# SCH___2025-06-27.net
KiCad netlist of a schematic drawn in EasyEDA
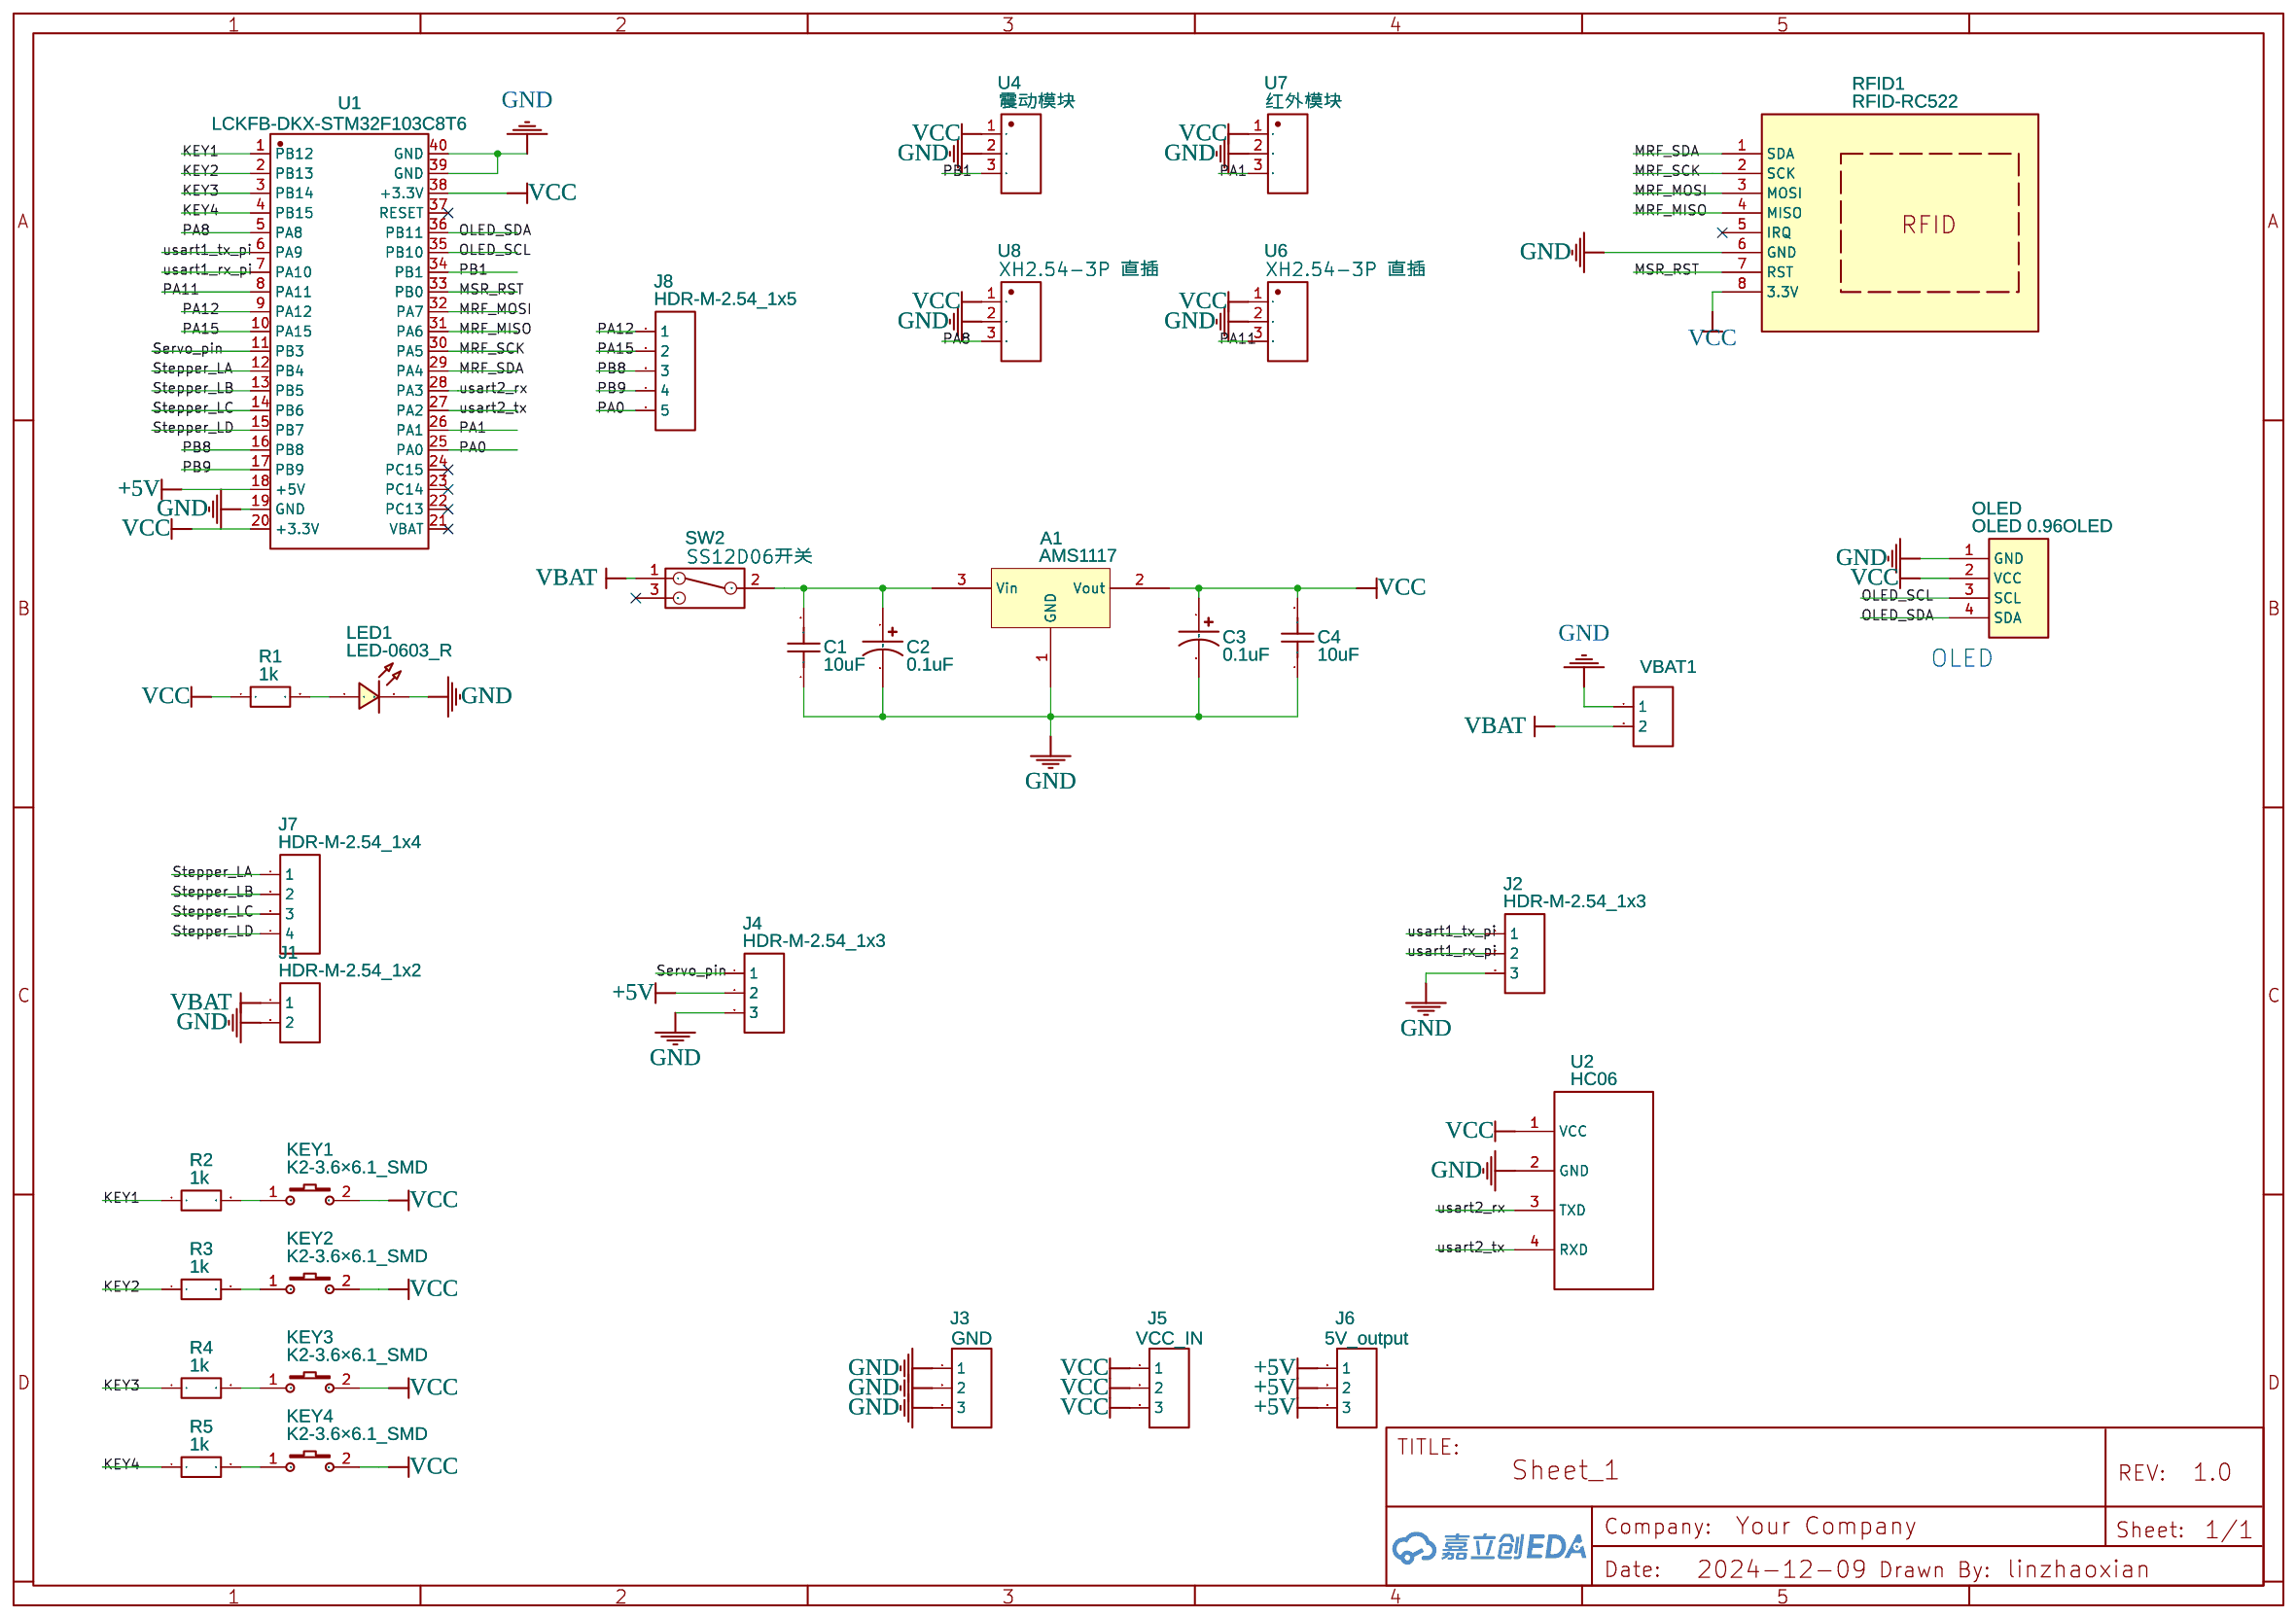
[diagram p0: schematic sheet]

(export (version "E")
  (design (tool "Eeschema 10.0.6"))
  (components
    (comp (ref "A1") (value "AMS1117") (libsource (lib "") (part "AMS1117")))
    (comp (ref "C1") (value "10uF") (libsource (lib "") (part "C_0603_US")))
    (comp (ref "C2") (value "0.1uF") (libsource (lib "") (part "C_Tan_SMD_A_US")))
    (comp (ref "C3") (value "0.1uF") (libsource (lib "") (part "C_Tan_SMD_A_US")))
    (comp (ref "C4") (value "10uF") (libsource (lib "") (part "C_0603_US")))
    (comp (ref "J1") (value "HDR-M-2.54_1x2") (libsource (lib "") (part "HDR-M-2.54_1x2")))
    (comp (ref "J2") (value "HDR-M-2.54_1x3") (libsource (lib "") (part "HDR-M-2.54_1x3")))
    (comp (ref "J3") (value "GND") (libsource (lib "") (part "HDR-M-2.54_1x3")))
    (comp (ref "J4") (value "HDR-M-2.54_1x3") (libsource (lib "") (part "HDR-M-2.54_1x3")))
    (comp (ref "J5") (value "VCC_IN") (libsource (lib "") (part "HDR-M-2.54_1x3")))
    (comp (ref "J6") (value "5V_output") (libsource (lib "") (part "HDR-M-2.54_1x3")))
    (comp (ref "J7") (value "HDR-M-2.54_1x4") (libsource (lib "") (part "HDR-M-2.54_1x4")))
    (comp (ref "J8") (value "HDR-M-2.54_1x5") (libsource (lib "") (part "HDR-M-2.54_1x5")))
    (comp (ref "KEY1")
      (value "K2-3.6×6.1_SMD")
      (fields (field (name "Manufacturer Part") "K2-1107ST-A4SW-06"))
      (libsource (lib "") (part "K2-3.6×6.1_SMD"))
    )
    (comp (ref "KEY2")
      (value "K2-3.6×6.1_SMD")
      (fields (field (name "Manufacturer Part") "K2-1107ST-A4SW-06"))
      (libsource (lib "") (part "K2-3.6×6.1_SMD"))
    )
    (comp (ref "KEY3")
      (value "K2-3.6×6.1_SMD")
      (fields (field (name "Manufacturer Part") "K2-1107ST-A4SW-06"))
      (libsource (lib "") (part "K2-3.6×6.1_SMD"))
    )
    (comp (ref "KEY4")
      (value "K2-3.6×6.1_SMD")
      (fields (field (name "Manufacturer Part") "K2-1107ST-A4SW-06"))
      (libsource (lib "") (part "K2-3.6×6.1_SMD"))
    )
    (comp (ref "LED1")
      (value "LED-0603_R")
      (fields
        (field (name "Manufacturer Part") "19-217/R6C-AL1M2VY/3T")
        (field (name "Manufacturer") "EVERLIGHT(台湾亿光)")
      )
      (libsource (lib "") (part "LED-0603_R"))
    )
    (comp (ref "OLED") (value "OLED 0.96OLED") (libsource (lib "") (part "OLED 0.96OLED")))
    (comp (ref "R1") (value "1k") (libsource (lib "") (part "R_0805_EU")))
    (comp (ref "R2") (value "1k") (libsource (lib "") (part "R_0805_EU")))
    (comp (ref "R3") (value "1k") (libsource (lib "") (part "R_0805_EU")))
    (comp (ref "R4") (value "1k") (libsource (lib "") (part "R_0805_EU")))
    (comp (ref "R5") (value "1k") (libsource (lib "") (part "R_0805_EU")))
    (comp (ref "RFID1") (value "RFID-RC522") (libsource (lib "") (part "RFID-RC522")))
    (comp (ref "SW2") (value "SS12D06开关") (libsource (lib "") (part "SS12D06开关")))
    (comp (ref "U1")
      (value "LCKFB-DKX-STM32F103C8T6")
      (fields (field (name "Manufacturer") "立创开发板"))
      (libsource (lib "") (part "LCKFB-DKX-STM32F103C8T6"))
    )
    (comp (ref "U2") (value "HC06") (libsource (lib "") (part "HC06")))
    (comp (ref "U4")
      (value "震动模块")
      (fields (field (name "Manufacturer Part") "XH2.54-3P 直插"))
      (libsource (lib "") (part "XH2.54-3P 直插"))
    )
    (comp (ref "U6") (value "XH2.54-3P 直插") (libsource (lib "") (part "XH2.54-3P 直插")))
    (comp (ref "U7")
      (value "红外模块")
      (fields (field (name "Manufacturer Part") "XH2.54-3P 直插"))
      (libsource (lib "") (part "XH2.54-3P 直插"))
    )
    (comp (ref "U8") (value "XH2.54-3P 直插") (libsource (lib "") (part "XH2.54-3P 直插")))
    (comp (ref "VBAT1") (value "端子") (libsource (lib "") (part "CONN-TH_2P-P5.00")))
  )
  (nets
    (net (code "1") (name "+5V") (class "Default")
      (node (ref "J4") (pin "2") (pinfunction "2_2") (pintype "input"))
      (node (ref "J6") (pin "1") (pinfunction "1_1") (pintype "input"))
      (node (ref "J6") (pin "2") (pinfunction "2_2") (pintype "input"))
      (node (ref "J6") (pin "3") (pinfunction "3_3") (pintype "input"))
      (node (ref "U1") (pin "18") (pinfunction "+5V_18") (pintype "unspecified"))
    )
    (net (code "2") (name "/KEY1") (class "Default")
      (node (ref "R2") (pin "1") (pinfunction "1_1") (pintype "unspecified"))
      (node (ref "U1") (pin "1") (pinfunction "PB12_1") (pintype "unspecified"))
    )
    (net (code "3") (name "/KEY2") (class "Default")
      (node (ref "R3") (pin "1") (pinfunction "1_1") (pintype "unspecified"))
      (node (ref "U1") (pin "2") (pinfunction "PB13_2") (pintype "unspecified"))
    )
    (net (code "4") (name "/KEY3") (class "Default")
      (node (ref "R4") (pin "1") (pinfunction "1_1") (pintype "unspecified"))
      (node (ref "U1") (pin "3") (pinfunction "PB14_3") (pintype "unspecified"))
    )
    (net (code "5") (name "/KEY4") (class "Default")
      (node (ref "R5") (pin "1") (pinfunction "1_1") (pintype "unspecified"))
      (node (ref "U1") (pin "4") (pinfunction "PB15_4") (pintype "unspecified"))
    )
    (net (code "6") (name "/MRF_MISO") (class "Default")
      (node (ref "RFID1") (pin "4") (pinfunction "MISO_4") (pintype "unspecified"))
      (node (ref "U1") (pin "31") (pinfunction "PA6_31") (pintype "unspecified"))
    )
    (net (code "7") (name "/MRF_MOSI") (class "Default")
      (node (ref "RFID1") (pin "3") (pinfunction "MOSI_3") (pintype "unspecified"))
      (node (ref "U1") (pin "32") (pinfunction "PA7_32") (pintype "unspecified"))
    )
    (net (code "8") (name "/MRF_SCK") (class "Default")
      (node (ref "RFID1") (pin "2") (pinfunction "SCK_2") (pintype "unspecified"))
      (node (ref "U1") (pin "30") (pinfunction "PA5_30") (pintype "unspecified"))
    )
    (net (code "9") (name "/MRF_SDA") (class "Default")
      (node (ref "RFID1") (pin "1") (pinfunction "SDA_1") (pintype "unspecified"))
      (node (ref "U1") (pin "29") (pinfunction "PA4_29") (pintype "unspecified"))
    )
    (net (code "10") (name "/MSR_RST") (class "Default")
      (node (ref "RFID1") (pin "7") (pinfunction "RST_7") (pintype "unspecified"))
      (node (ref "U1") (pin "33") (pinfunction "PB0_33") (pintype "unspecified"))
    )
    (net (code "11") (name "/OLED_SCL") (class "Default")
      (node (ref "OLED") (pin "3") (pinfunction "SCL_3") (pintype "unspecified"))
      (node (ref "U1") (pin "35") (pinfunction "PB10_35") (pintype "unspecified"))
    )
    (net (code "12") (name "/OLED_SDA") (class "Default")
      (node (ref "OLED") (pin "4") (pinfunction "SDA_4") (pintype "unspecified"))
      (node (ref "U1") (pin "36") (pinfunction "PB11_36") (pintype "unspecified"))
    )
    (net (code "13") (name "/PA0") (class "Default")
      (node (ref "J8") (pin "5") (pinfunction "5_5") (pintype "unspecified"))
      (node (ref "U1") (pin "25") (pinfunction "PA0_25") (pintype "unspecified"))
    )
    (net (code "14") (name "/PA1") (class "Default")
      (node (ref "U1") (pin "26") (pinfunction "PA1_26") (pintype "unspecified"))
      (node (ref "U7") (pin "3") (pinfunction "3_3") (pintype "unspecified"))
    )
    (net (code "15") (name "/PA8") (class "Default")
      (node (ref "U1") (pin "5") (pinfunction "PA8_5") (pintype "unspecified"))
      (node (ref "U8") (pin "3") (pinfunction "3_3") (pintype "unspecified"))
    )
    (net (code "16") (name "/PA11") (class "Default")
      (node (ref "U1") (pin "8") (pinfunction "PA11_8") (pintype "unspecified"))
      (node (ref "U6") (pin "3") (pinfunction "3_3") (pintype "unspecified"))
    )
    (net (code "17") (name "/PA12") (class "Default")
      (node (ref "J8") (pin "1") (pinfunction "1_1") (pintype "unspecified"))
      (node (ref "U1") (pin "9") (pinfunction "PA12_9") (pintype "unspecified"))
    )
    (net (code "18") (name "/PA15") (class "Default")
      (node (ref "J8") (pin "2") (pinfunction "2_2") (pintype "unspecified"))
      (node (ref "U1") (pin "10") (pinfunction "PA15_10") (pintype "unspecified"))
    )
    (net (code "19") (name "/PB1") (class "Default")
      (node (ref "U1") (pin "34") (pinfunction "PB1_34") (pintype "unspecified"))
      (node (ref "U4") (pin "3") (pinfunction "3_3") (pintype "unspecified"))
    )
    (net (code "20") (name "/PB8") (class "Default")
      (node (ref "J8") (pin "3") (pinfunction "3_3") (pintype "unspecified"))
      (node (ref "U1") (pin "16") (pinfunction "PB8_16") (pintype "unspecified"))
    )
    (net (code "21") (name "/PB9") (class "Default")
      (node (ref "J8") (pin "4") (pinfunction "4_4") (pintype "unspecified"))
      (node (ref "U1") (pin "17") (pinfunction "PB9_17") (pintype "unspecified"))
    )
    (net (code "22") (name "/Servo_pin") (class "Default")
      (node (ref "J4") (pin "1") (pinfunction "1_1") (pintype "input"))
      (node (ref "U1") (pin "11") (pinfunction "PB3_11") (pintype "unspecified"))
    )
    (net (code "23") (name "/Stepper_LA") (class "Default")
      (node (ref "J7") (pin "1") (pinfunction "1_1") (pintype "unspecified"))
      (node (ref "U1") (pin "12") (pinfunction "PB4_12") (pintype "unspecified"))
    )
    (net (code "24") (name "/Stepper_LB") (class "Default")
      (node (ref "J7") (pin "2") (pinfunction "2_2") (pintype "unspecified"))
      (node (ref "U1") (pin "13") (pinfunction "PB5_13") (pintype "unspecified"))
    )
    (net (code "25") (name "/Stepper_LC") (class "Default")
      (node (ref "J7") (pin "3") (pinfunction "3_3") (pintype "unspecified"))
      (node (ref "U1") (pin "14") (pinfunction "PB6_14") (pintype "unspecified"))
    )
    (net (code "26") (name "/Stepper_LD") (class "Default")
      (node (ref "J7") (pin "4") (pinfunction "4_4") (pintype "unspecified"))
      (node (ref "U1") (pin "15") (pinfunction "PB7_15") (pintype "unspecified"))
    )
    (net (code "27") (name "/usart1_rx_pi") (class "Default")
      (node (ref "J2") (pin "2") (pinfunction "2_2") (pintype "input"))
      (node (ref "U1") (pin "7") (pinfunction "PA10_7") (pintype "unspecified"))
    )
    (net (code "28") (name "/usart1_tx_pi") (class "Default")
      (node (ref "J2") (pin "1") (pinfunction "1_1") (pintype "input"))
      (node (ref "U1") (pin "6") (pinfunction "PA9_6") (pintype "unspecified"))
    )
    (net (code "29") (name "/usart2_rx") (class "Default")
      (node (ref "U1") (pin "28") (pinfunction "PA3_28") (pintype "unspecified"))
      (node (ref "U2") (pin "3") (pinfunction "TXD_3") (pintype "unspecified"))
    )
    (net (code "30") (name "/usart2_tx") (class "Default")
      (node (ref "U1") (pin "27") (pinfunction "PA2_27") (pintype "unspecified"))
      (node (ref "U2") (pin "4") (pinfunction "RXD_4") (pintype "unspecified"))
    )
    (net (code "31") (name "GND") (class "Default")
      (node (ref "A1") (pin "1") (pinfunction "GND_1") (pintype "unspecified"))
      (node (ref "C1") (pin "1") (pinfunction "1_1") (pintype "unspecified"))
      (node (ref "C2") (pin "2") (pinfunction "2_2") (pintype "unspecified"))
      (node (ref "C3") (pin "2") (pinfunction "2_2") (pintype "unspecified"))
      (node (ref "C4") (pin "1") (pinfunction "1_1") (pintype "unspecified"))
      (node (ref "J1") (pin "2") (pinfunction "2_2") (pintype "unspecified"))
      (node (ref "J2") (pin "3") (pinfunction "3_3") (pintype "input"))
      (node (ref "J3") (pin "1") (pinfunction "1_1") (pintype "input"))
      (node (ref "J3") (pin "2") (pinfunction "2_2") (pintype "input"))
      (node (ref "J3") (pin "3") (pinfunction "3_3") (pintype "input"))
      (node (ref "J4") (pin "3") (pinfunction "3_3") (pintype "input"))
      (node (ref "LED1") (pin "2") (pinfunction "2_2") (pintype "unspecified"))
      (node (ref "OLED") (pin "1") (pinfunction "GND_1") (pintype "unspecified"))
      (node (ref "RFID1") (pin "6") (pinfunction "GND_6") (pintype "unspecified"))
      (node (ref "U1") (pin "19") (pinfunction "GND_19") (pintype "unspecified"))
      (node (ref "U1") (pin "39") (pinfunction "GND_39") (pintype "unspecified"))
      (node (ref "U1") (pin "40") (pinfunction "GND_40") (pintype "unspecified"))
      (node (ref "U2") (pin "2") (pinfunction "GND_2") (pintype "unspecified"))
      (node (ref "U4") (pin "2") (pinfunction "2_2") (pintype "unspecified"))
      (node (ref "U6") (pin "2") (pinfunction "2_2") (pintype "unspecified"))
      (node (ref "U7") (pin "2") (pinfunction "2_2") (pintype "unspecified"))
      (node (ref "U8") (pin "2") (pinfunction "2_2") (pintype "unspecified"))
      (node (ref "VBAT1") (pin "1") (pinfunction "1_1") (pintype "unspecified"))
    )
    (net (code "32") (name "Net-(A1-Vin)") (class "Default")
      (node (ref "A1") (pin "3") (pinfunction "Vin_3") (pintype "unspecified"))
      (node (ref "C1") (pin "2") (pinfunction "2_2") (pintype "unspecified"))
      (node (ref "C2") (pin "1") (pinfunction "1_1") (pintype "unspecified"))
      (node (ref "SW2") (pin "2") (pinfunction "2_2") (pintype "unspecified"))
    )
    (net (code "33") (name "Net-(KEY1-Pad1)") (class "Default")
      (node (ref "KEY1") (pin "1") (pinfunction "1_1") (pintype "unspecified"))
      (node (ref "R2") (pin "2") (pinfunction "2_2") (pintype "unspecified"))
    )
    (net (code "34") (name "Net-(KEY2-Pad1)") (class "Default")
      (node (ref "KEY2") (pin "1") (pinfunction "1_1") (pintype "unspecified"))
      (node (ref "R3") (pin "2") (pinfunction "2_2") (pintype "unspecified"))
    )
    (net (code "35") (name "Net-(KEY3-Pad1)") (class "Default")
      (node (ref "KEY3") (pin "1") (pinfunction "1_1") (pintype "unspecified"))
      (node (ref "R4") (pin "2") (pinfunction "2_2") (pintype "unspecified"))
    )
    (net (code "36") (name "Net-(KEY4-Pad1)") (class "Default")
      (node (ref "KEY4") (pin "1") (pinfunction "1_1") (pintype "unspecified"))
      (node (ref "R5") (pin "2") (pinfunction "2_2") (pintype "unspecified"))
    )
    (net (code "37") (name "Net-(LED1-Pad1)") (class "Default")
      (node (ref "LED1") (pin "1") (pinfunction "1_1") (pintype "unspecified"))
      (node (ref "R1") (pin "2") (pinfunction "2_2") (pintype "unspecified"))
    )
    (net (code "38") (name "VBAT") (class "Default")
      (node (ref "J1") (pin "1") (pinfunction "1_1") (pintype "unspecified"))
      (node (ref "SW2") (pin "1") (pinfunction "1_1") (pintype "unspecified"))
      (node (ref "VBAT1") (pin "2") (pinfunction "2_2") (pintype "unspecified"))
    )
    (net (code "39") (name "VCC") (class "Default")
      (node (ref "A1") (pin "2") (pinfunction "Vout_2") (pintype "unspecified"))
      (node (ref "C3") (pin "1") (pinfunction "1_1") (pintype "unspecified"))
      (node (ref "C4") (pin "2") (pinfunction "2_2") (pintype "unspecified"))
      (node (ref "J5") (pin "1") (pinfunction "1_1") (pintype "input"))
      (node (ref "J5") (pin "2") (pinfunction "2_2") (pintype "input"))
      (node (ref "J5") (pin "3") (pinfunction "3_3") (pintype "input"))
      (node (ref "KEY1") (pin "2") (pinfunction "2_2") (pintype "unspecified"))
      (node (ref "KEY2") (pin "2") (pinfunction "2_2") (pintype "unspecified"))
      (node (ref "KEY3") (pin "2") (pinfunction "2_2") (pintype "unspecified"))
      (node (ref "KEY4") (pin "2") (pinfunction "2_2") (pintype "unspecified"))
      (node (ref "OLED") (pin "2") (pinfunction "VCC_2") (pintype "unspecified"))
      (node (ref "R1") (pin "1") (pinfunction "1_1") (pintype "unspecified"))
      (node (ref "RFID1") (pin "8") (pinfunction "3.3V_8") (pintype "unspecified"))
      (node (ref "U1") (pin "20") (pinfunction "+3.3V_20") (pintype "unspecified"))
      (node (ref "U1") (pin "38") (pinfunction "+3.3V_38") (pintype "unspecified"))
      (node (ref "U2") (pin "1") (pinfunction "VCC_1") (pintype "unspecified"))
      (node (ref "U4") (pin "1") (pinfunction "1_1") (pintype "unspecified"))
      (node (ref "U6") (pin "1") (pinfunction "1_1") (pintype "unspecified"))
      (node (ref "U7") (pin "1") (pinfunction "1_1") (pintype "unspecified"))
      (node (ref "U8") (pin "1") (pinfunction "1_1") (pintype "unspecified"))
    )
    (net (code "40") (name "unconnected-(RFID1-IRQ-Pad5)") (class "Default")
      (node (ref "RFID1") (pin "5") (pinfunction "IRQ_5") (pintype "unspecified+no_connect"))
    )
    (net (code "41") (name "unconnected-(SW2-Pad3)") (class "Default")
      (node (ref "SW2") (pin "3") (pinfunction "3_3") (pintype "unspecified+no_connect"))
    )
    (net (code "42") (name "unconnected-(U1-PC13-Pad22)") (class "Default")
      (node (ref "U1") (pin "22") (pinfunction "PC13_22") (pintype "unspecified+no_connect"))
    )
    (net (code "43") (name "unconnected-(U1-PC14-Pad23)") (class "Default")
      (node (ref "U1") (pin "23") (pinfunction "PC14_23") (pintype "unspecified+no_connect"))
    )
    (net (code "44") (name "unconnected-(U1-PC15-Pad24)") (class "Default")
      (node (ref "U1") (pin "24") (pinfunction "PC15_24") (pintype "unspecified+no_connect"))
    )
    (net (code "45") (name "unconnected-(U1-RESET-Pad37)") (class "Default")
      (node (ref "U1") (pin "37") (pinfunction "RESET_37") (pintype "unspecified+no_connect"))
    )
    (net (code "46") (name "unconnected-(U1-VBAT-Pad21)") (class "Default")
      (node (ref "U1") (pin "21") (pinfunction "VBAT_21") (pintype "unspecified+no_connect"))
    )
  )
)
